# working.net
KiCad netlist of a schematic drawn in EAGLE
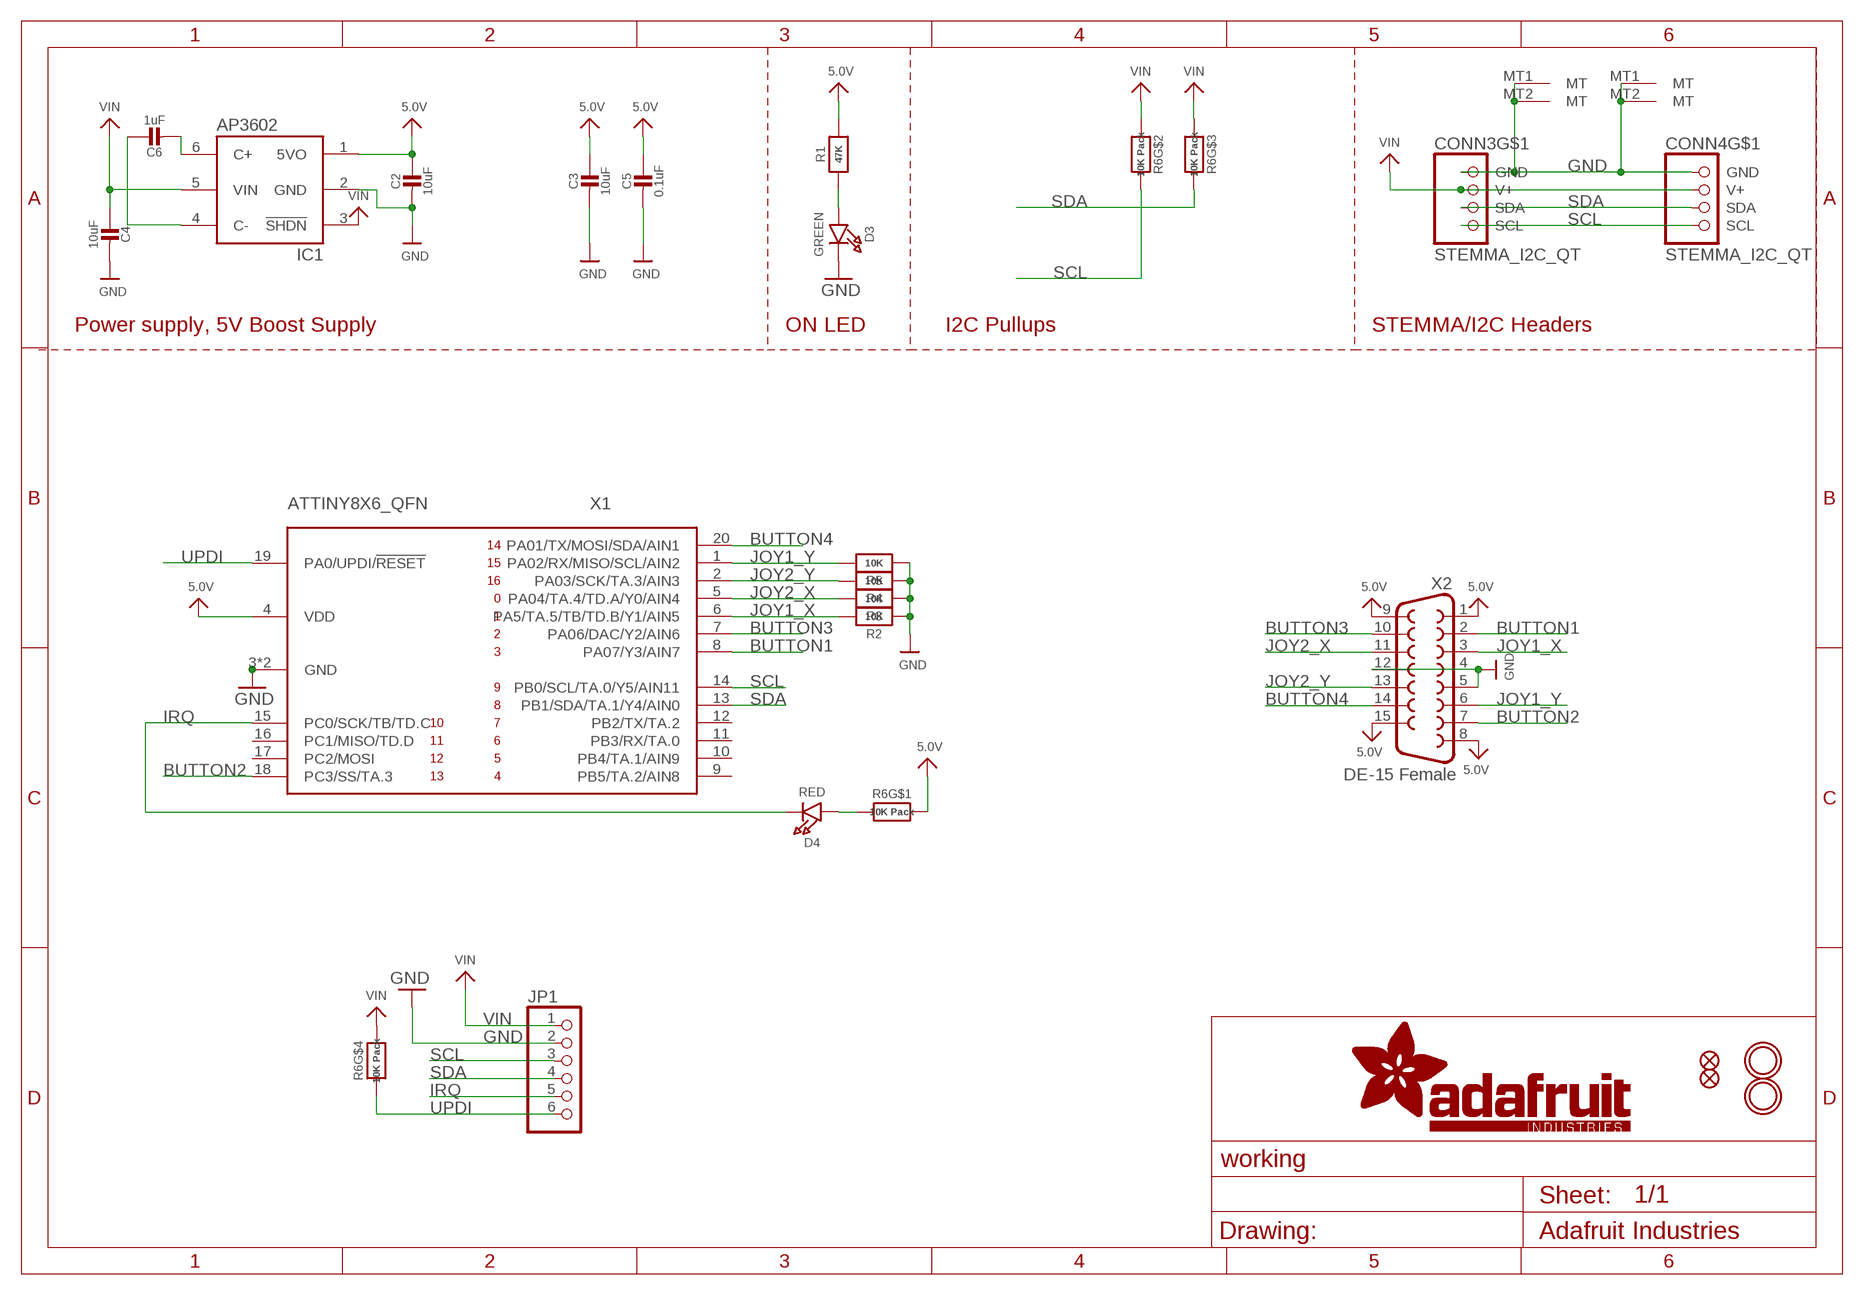
[diagram p0: schematic, sheet 1]

(export (version "E")
  (design (tool "Eeschema 10.0.6"))
  (components
    (comp (ref "C2")
      (value "10uF")
      (footprint "eagle-import:0805-NO")
      (libsource (lib "eagle-import") (part "CAP_CERAMIC0805-NOOUTLINE"))
    )
    (comp (ref "C3")
      (value "10uF")
      (footprint "eagle-import:0805-NO")
      (libsource (lib "eagle-import") (part "CAP_CERAMIC0805-NOOUTLINE"))
    )
    (comp (ref "C4")
      (value "10uF")
      (footprint "eagle-import:0805-NO")
      (libsource (lib "eagle-import") (part "CAP_CERAMIC0805-NOOUTLINE"))
    )
    (comp (ref "C5")
      (value "0.1uF")
      (footprint "eagle-import:0603-NO")
      (libsource (lib "eagle-import") (part "CAP_CERAMIC0603_NO"))
    )
    (comp (ref "C6")
      (value "1uF")
      (footprint "eagle-import:0603-NO")
      (libsource (lib "eagle-import") (part "CAP_CERAMIC0603_NO"))
    )
    (comp (ref "CONN3")
      (value "STEMMA_I2C_QT")
      (footprint "eagle-import:JST_SH4")
      (libsource (lib "eagle-import") (part "STEMMA_I2C_QT"))
    )
    (comp (ref "CONN4")
      (value "STEMMA_I2C_QT")
      (footprint "eagle-import:JST_SH4")
      (libsource (lib "eagle-import") (part "STEMMA_I2C_QT"))
    )
    (comp (ref "D3")
      (value "GREEN")
      (footprint "eagle-import:CHIPLED_0603_NOOUTLINE")
      (libsource (lib "eagle-import") (part "LED0603_NOOUTLINE"))
    )
    (comp (ref "D4")
      (value "RED")
      (footprint "eagle-import:CHIPLED_0603_NOOUTLINE")
      (libsource (lib "eagle-import") (part "LED0603_NOOUTLINE"))
    )
    (comp (ref "FID1")
      (value "FIDUCIAL_1MM")
      (footprint "eagle-import:FIDUCIAL_1MM")
      (libsource (lib "eagle-import") (part "FIDUCIAL_1MM"))
    )
    (comp (ref "FID2")
      (value "FIDUCIAL_1MM")
      (footprint "eagle-import:FIDUCIAL_1MM")
      (libsource (lib "eagle-import") (part "FIDUCIAL_1MM"))
    )
    (comp (ref "IC1")
      (value "AP3602")
      (footprint "eagle-import:SOT23-6")
      (libsource (lib "eagle-import") (part "AP3602"))
    )
    (comp (ref "JP1")
      (value "HEADER-1X670MIL")
      (footprint "eagle-import:1X06_ROUND_70")
      (libsource (lib "eagle-import") (part "HEADER-1X670MIL"))
    )
    (comp (ref "R1")
      (value "47K")
      (footprint "eagle-import:0603-NO")
      (libsource (lib "eagle-import") (part "RESISTOR_0603_NOOUT"))
    )
    (comp (ref "R2")
      (value "10K")
      (footprint "eagle-import:0603-NO")
      (libsource (lib "eagle-import") (part "RESISTOR_0603_NOOUT"))
    )
    (comp (ref "R3")
      (value "10K")
      (footprint "eagle-import:0603-NO")
      (libsource (lib "eagle-import") (part "RESISTOR_0603_NOOUT"))
    )
    (comp (ref "R4")
      (value "10K")
      (footprint "eagle-import:0603-NO")
      (libsource (lib "eagle-import") (part "RESISTOR_0603_NOOUT"))
    )
    (comp (ref "R5")
      (value "10K")
      (footprint "eagle-import:0603-NO")
      (libsource (lib "eagle-import") (part "RESISTOR_0603_NOOUT"))
    )
    (comp (ref "R6")
      (value "10K Pack")
      (footprint "eagle-import:RESPACK_4X0603")
      (libsource (lib "eagle-import") (part "RESISTOR_4PACK"))
    )
    (comp (ref "U$6")
      (value "MOUNTINGHOLE2.5")
      (footprint "eagle-import:MOUNTINGHOLE_2.5_PLATED")
      (libsource (lib "eagle-import") (part "MOUNTINGHOLE2.5"))
    )
    (comp (ref "U$18")
      (value "MOUNTINGHOLE2.5")
      (footprint "eagle-import:MOUNTINGHOLE_2.5_PLATED")
      (libsource (lib "eagle-import") (part "MOUNTINGHOLE2.5"))
    )
    (comp (ref "X1")
      (value "ATTINY8X6_QFN")
      (footprint "eagle-import:QFN20_3MM")
      (libsource (lib "eagle-import") (part "ATTINY8X6_QFN"))
    )
    (comp (ref "X2")
      (value "DE-15 Female")
      (footprint "eagle-import:F15H")
      (libsource (lib "eagle-import") (part "F15H"))
    )
  )
  (nets
    (net (code "1") (name "/BUTTON1") (class "Default")
      (node (ref "X1") (pin "8") (pinfunction "PA07/Y3/AIN7_8") (pintype "bidirectional"))
      (node (ref "X2") (pin "2") (pinfunction "2_2") (pintype "passive"))
    )
    (net (code "2") (name "/BUTTON2") (class "Default")
      (node (ref "X1") (pin "18") (pinfunction "PC3/SS/TA.3_18") (pintype "bidirectional"))
      (node (ref "X2") (pin "7") (pinfunction "7_7") (pintype "passive"))
    )
    (net (code "3") (name "/BUTTON3") (class "Default")
      (node (ref "X1") (pin "7") (pinfunction "PA06/DAC/Y2/AIN6_7") (pintype "bidirectional"))
      (node (ref "X2") (pin "10") (pinfunction "10_10") (pintype "passive"))
    )
    (net (code "4") (name "/BUTTON4") (class "Default")
      (node (ref "X1") (pin "20") (pinfunction "PA01/TX/MOSI/SDA/AIN1_20") (pintype "bidirectional"))
      (node (ref "X2") (pin "14") (pinfunction "14_14") (pintype "passive"))
    )
    (net (code "5") (name "/IRQ") (class "Default")
      (node (ref "D4") (pin "C") (pinfunction "C_C") (pintype "passive"))
      (node (ref "JP1") (pin "5") (pinfunction "5_5") (pintype "passive"))
      (node (ref "X1") (pin "15") (pinfunction "PC0/SCK/TB/TD.C_15") (pintype "bidirectional"))
    )
    (net (code "6") (name "/JOY1_X") (class "Default")
      (node (ref "R2") (pin "2") (pinfunction "2_2") (pintype "passive"))
      (node (ref "X1") (pin "6") (pinfunction "PA5/TA.5/TB/TD.B/Y1/AIN5_6") (pintype "bidirectional"))
      (node (ref "X2") (pin "3") (pinfunction "3_3") (pintype "passive"))
    )
    (net (code "7") (name "/JOY1_Y") (class "Default")
      (node (ref "R5") (pin "2") (pinfunction "2_2") (pintype "passive"))
      (node (ref "X1") (pin "1") (pinfunction "PA02/RX/MISO/SCL/AIN2_1") (pintype "bidirectional"))
      (node (ref "X2") (pin "6") (pinfunction "6_6") (pintype "passive"))
    )
    (net (code "8") (name "/JOY2_X") (class "Default")
      (node (ref "R3") (pin "2") (pinfunction "2_2") (pintype "passive"))
      (node (ref "X1") (pin "5") (pinfunction "PA04/TA.4/TD.A/Y0/AIN4_5") (pintype "bidirectional"))
      (node (ref "X2") (pin "11") (pinfunction "11_11") (pintype "passive"))
    )
    (net (code "9") (name "/JOY2_Y") (class "Default")
      (node (ref "R4") (pin "2") (pinfunction "2_2") (pintype "passive"))
      (node (ref "X1") (pin "2") (pinfunction "PA03/SCK/TA.3/AIN3_2") (pintype "bidirectional"))
      (node (ref "X2") (pin "13") (pinfunction "13_13") (pintype "passive"))
    )
    (net (code "10") (name "/SCL") (class "Default")
      (node (ref "CONN3") (pin "4") (pinfunction "SCL_4") (pintype "passive"))
      (node (ref "CONN4") (pin "4") (pinfunction "SCL_4") (pintype "passive"))
      (node (ref "JP1") (pin "3") (pinfunction "3_3") (pintype "passive"))
      (node (ref "R6") (pin "7") (pinfunction "2_7") (pintype "passive"))
      (node (ref "X1") (pin "14") (pinfunction "PB0/SCL/TA.0/Y5/AIN11_14") (pintype "bidirectional"))
    )
    (net (code "11") (name "/SDA") (class "Default")
      (node (ref "CONN3") (pin "3") (pinfunction "SDA_3") (pintype "passive"))
      (node (ref "CONN4") (pin "3") (pinfunction "SDA_3") (pintype "passive"))
      (node (ref "JP1") (pin "4") (pinfunction "4_4") (pintype "passive"))
      (node (ref "R6") (pin "6") (pinfunction "2_6") (pintype "passive"))
      (node (ref "X1") (pin "13") (pinfunction "PB1/SDA/TA.1/Y4/AIN0_13") (pintype "bidirectional"))
    )
    (net (code "12") (name "/UPDI") (class "Default")
      (node (ref "JP1") (pin "6") (pinfunction "6_6") (pintype "passive"))
      (node (ref "R6") (pin "4") (pinfunction "1_4") (pintype "passive"))
      (node (ref "X1") (pin "19") (pinfunction "PA0/UPDI/~{RESET}_19") (pintype "bidirectional"))
    )
    (net (code "13") (name "5.0V") (class "Default")
      (node (ref "C2") (pin "1") (pinfunction "1_1") (pintype "passive"))
      (node (ref "C3") (pin "1") (pinfunction "1_1") (pintype "passive"))
      (node (ref "C5") (pin "1") (pinfunction "1_1") (pintype "passive"))
      (node (ref "IC1") (pin "1") (pinfunction "5VO_1") (pintype "power_in"))
      (node (ref "R1") (pin "2") (pinfunction "2_2") (pintype "passive"))
      (node (ref "R6") (pin "8") (pinfunction "2_8") (pintype "passive"))
      (node (ref "X1") (pin "4") (pinfunction "VDD_4") (pintype "power_in"))
      (node (ref "X2") (pin "1") (pinfunction "1_1") (pintype "passive"))
      (node (ref "X2") (pin "15") (pinfunction "15_15") (pintype "passive"))
      (node (ref "X2") (pin "8") (pinfunction "8_8") (pintype "passive"))
      (node (ref "X2") (pin "9") (pinfunction "9_9") (pintype "passive"))
    )
    (net (code "14") (name "GND") (class "Default")
      (node (ref "C2") (pin "2") (pinfunction "2_2") (pintype "passive"))
      (node (ref "C3") (pin "2") (pinfunction "2_2") (pintype "passive"))
      (node (ref "C4") (pin "2") (pinfunction "2_2") (pintype "passive"))
      (node (ref "C5") (pin "2") (pinfunction "2_2") (pintype "passive"))
      (node (ref "CONN3") (pin "1") (pinfunction "GND_1") (pintype "passive"))
      (node (ref "CONN3") (pin "MT1") (pinfunction "MT_MT1") (pintype "bidirectional"))
      (node (ref "CONN3") (pin "MT2") (pinfunction "MT_MT2") (pintype "bidirectional"))
      (node (ref "CONN4") (pin "1") (pinfunction "GND_1") (pintype "passive"))
      (node (ref "CONN4") (pin "MT1") (pinfunction "MT_MT1") (pintype "bidirectional"))
      (node (ref "CONN4") (pin "MT2") (pinfunction "MT_MT2") (pintype "bidirectional"))
      (node (ref "D3") (pin "C") (pinfunction "C_C") (pintype "passive"))
      (node (ref "IC1") (pin "2") (pinfunction "GND_2") (pintype "power_in"))
      (node (ref "JP1") (pin "2") (pinfunction "2_2") (pintype "passive"))
      (node (ref "R2") (pin "1") (pinfunction "1_1") (pintype "passive"))
      (node (ref "R3") (pin "1") (pinfunction "1_1") (pintype "passive"))
      (node (ref "R4") (pin "1") (pinfunction "1_1") (pintype "passive"))
      (node (ref "R5") (pin "1") (pinfunction "1_1") (pintype "passive"))
      (node (ref "X1") (pin "3") (pinfunction "GND_3") (pintype "power_in"))
      (node (ref "X1") (pin "PAD") (pinfunction "GND_PAD") (pintype "power_in"))
      (node (ref "X2") (pin "12") (pinfunction "12_12") (pintype "passive"))
      (node (ref "X2") (pin "4") (pinfunction "4_4") (pintype "passive"))
      (node (ref "X2") (pin "5") (pinfunction "5_5") (pintype "passive"))
    )
    (net (code "15") (name "Net-(D3-PadA)") (class "Default")
      (node (ref "D3") (pin "A") (pinfunction "A_A") (pintype "passive"))
      (node (ref "R1") (pin "1") (pinfunction "1_1") (pintype "passive"))
    )
    (net (code "16") (name "Net-(D4-PadA)") (class "Default")
      (node (ref "D4") (pin "A") (pinfunction "A_A") (pintype "passive"))
      (node (ref "R6") (pin "1") (pinfunction "1_1") (pintype "passive"))
    )
    (net (code "17") (name "Net-(IC1-C+)") (class "Default")
      (node (ref "C6") (pin "2") (pinfunction "2_2") (pintype "passive"))
      (node (ref "IC1") (pin "6") (pinfunction "C+_6") (pintype "bidirectional"))
    )
    (net (code "18") (name "Net-(IC1-C-)") (class "Default")
      (node (ref "C6") (pin "1") (pinfunction "1_1") (pintype "passive"))
      (node (ref "IC1") (pin "4") (pinfunction "C-_4") (pintype "bidirectional"))
    )
    (net (code "19") (name "VIN") (class "Default")
      (node (ref "C4") (pin "1") (pinfunction "1_1") (pintype "passive"))
      (node (ref "CONN3") (pin "2") (pinfunction "V+_2") (pintype "passive"))
      (node (ref "CONN4") (pin "2") (pinfunction "V+_2") (pintype "passive"))
      (node (ref "IC1") (pin "3") (pinfunction "~{SHDN}_3") (pintype "input"))
      (node (ref "IC1") (pin "5") (pinfunction "VIN_5") (pintype "power_in"))
      (node (ref "JP1") (pin "1") (pinfunction "1_1") (pintype "passive"))
      (node (ref "R6") (pin "2") (pinfunction "1_2") (pintype "passive"))
      (node (ref "R6") (pin "3") (pinfunction "1_3") (pintype "passive"))
      (node (ref "R6") (pin "5") (pinfunction "2_5") (pintype "passive"))
    )
    (net (code "20") (name "unconnected-(X1-PB2{slash}TX{slash}TA.2-Pad12)") (class "Default")
      (node (ref "X1") (pin "12") (pinfunction "PB2/TX/TA.2_12") (pintype "bidirectional"))
    )
    (net (code "21") (name "unconnected-(X1-PB3{slash}RX{slash}TA.0-Pad11)") (class "Default")
      (node (ref "X1") (pin "11") (pinfunction "PB3/RX/TA.0_11") (pintype "bidirectional"))
    )
    (net (code "22") (name "unconnected-(X1-PB4{slash}TA.1{slash}AIN9-Pad10)") (class "Default")
      (node (ref "X1") (pin "10") (pinfunction "PB4/TA.1/AIN9_10") (pintype "bidirectional"))
    )
    (net (code "23") (name "unconnected-(X1-PB5{slash}TA.2{slash}AIN8-Pad9)") (class "Default")
      (node (ref "X1") (pin "9") (pinfunction "PB5/TA.2/AIN8_9") (pintype "bidirectional"))
    )
    (net (code "24") (name "unconnected-(X1-PC1{slash}MISO{slash}TD.D-Pad16)") (class "Default")
      (node (ref "X1") (pin "16") (pinfunction "PC1/MISO/TD.D_16") (pintype "bidirectional"))
    )
    (net (code "25") (name "unconnected-(X1-PC2{slash}MOSI-Pad17)") (class "Default")
      (node (ref "X1") (pin "17") (pinfunction "PC2/MOSI_17") (pintype "bidirectional"))
    )
  )
)
